# Proiect_TSC_schematic.net
KiCad netlist of a schematic drawn in EAGLE
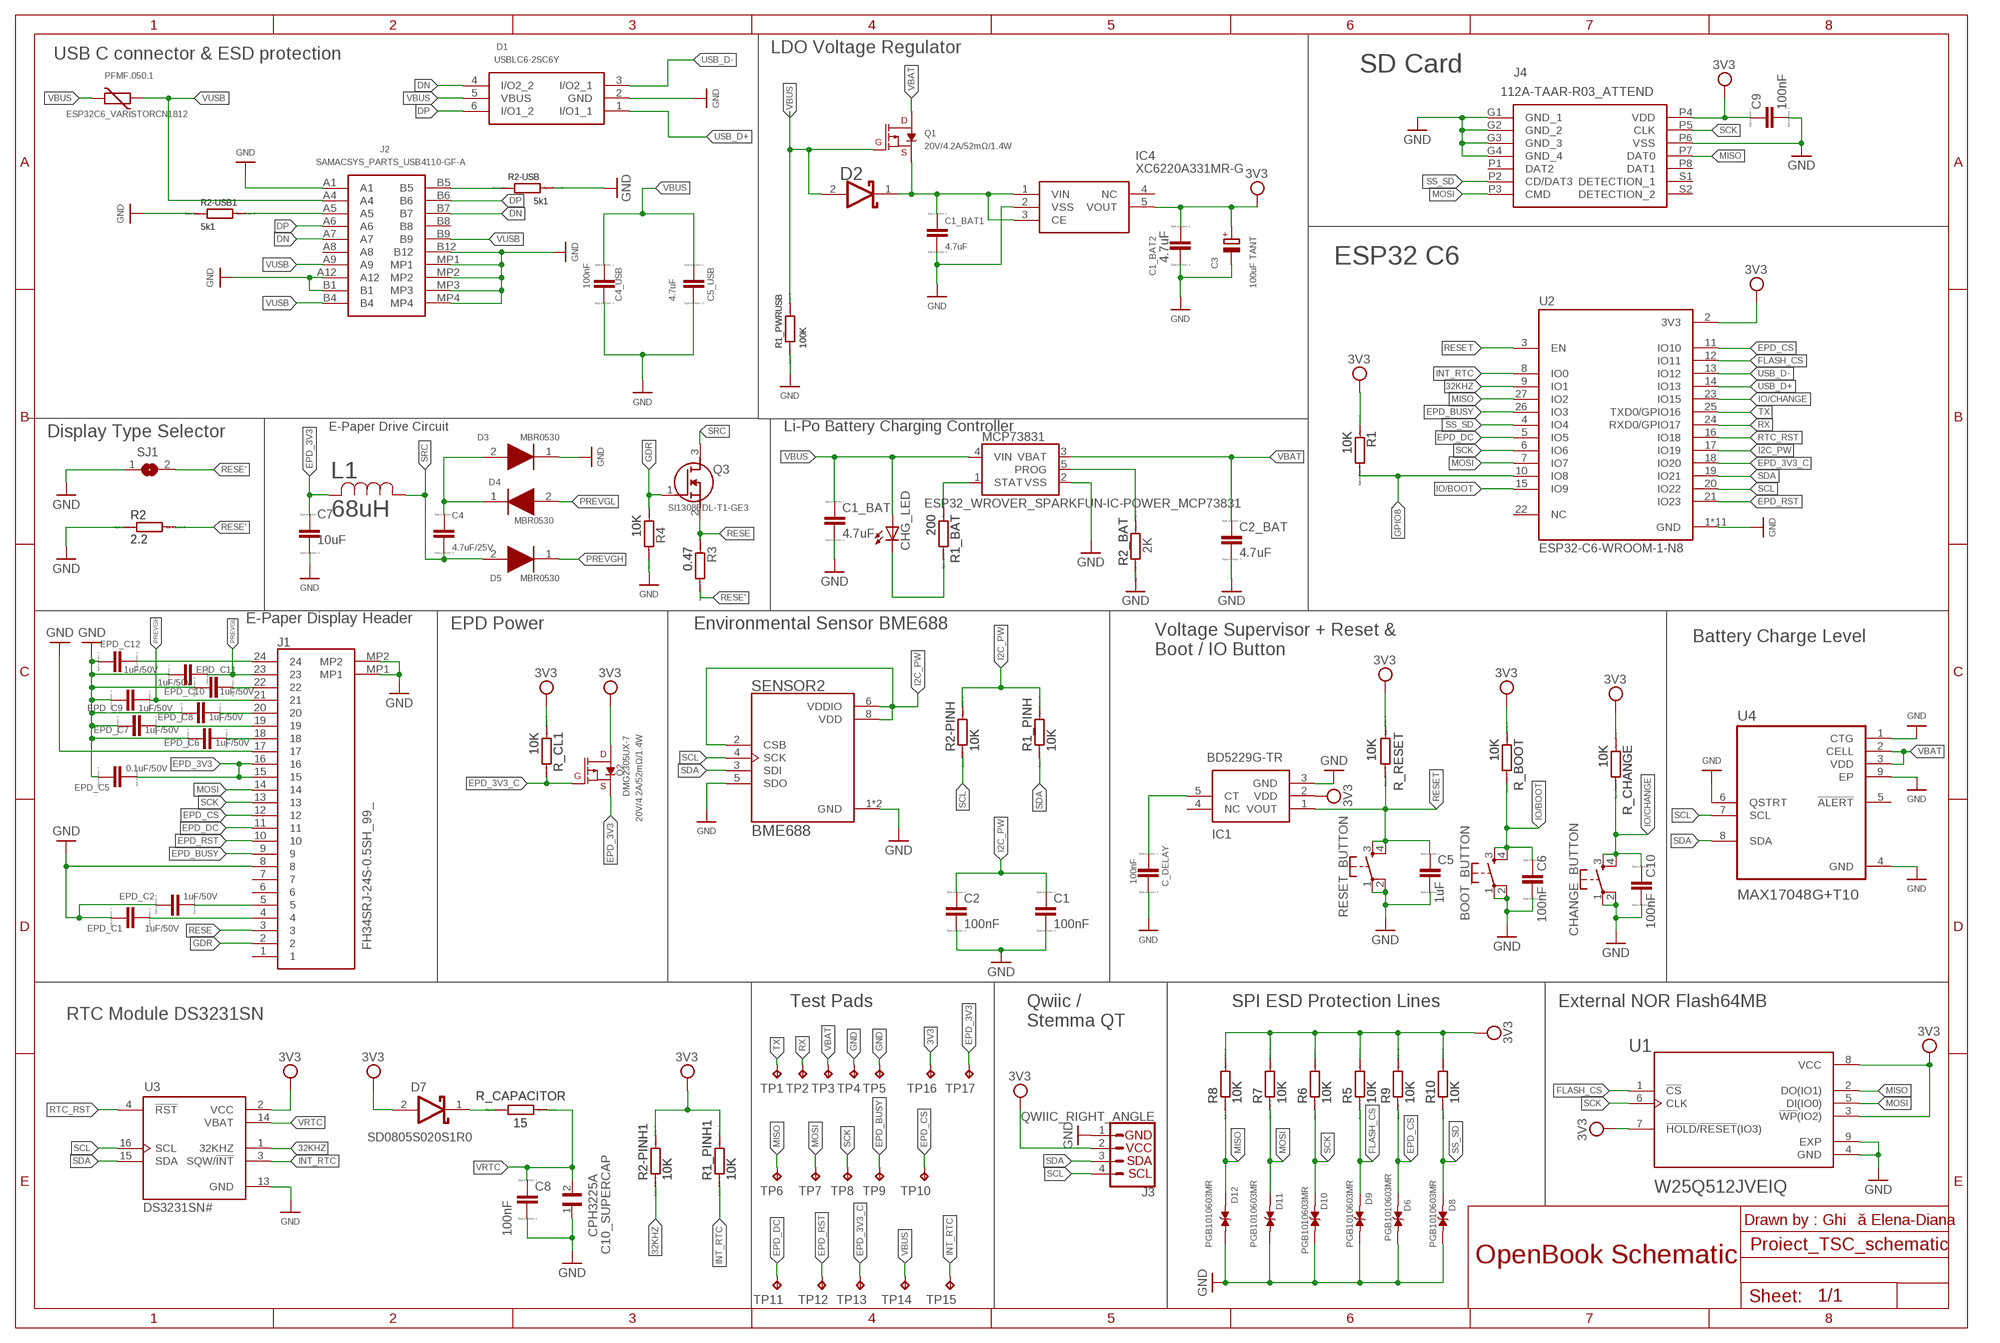
[diagram p0: schematic, sheet 1]

(export (version "E")
  (design (tool "Eeschema 10.0.6"))
  (components
    (comp (ref "BOOT_BUTTON")
      (value "BUTTON_CUSYOMV1")
      (footprint "eagle-import:MYBUTTON")
      (libsource (lib "eagle-import") (part "BUTTON_CUSYOMV1"))
    )
    (comp (ref "C1")
      (value "100nF")
      (footprint "eagle-import:ESP32_WROVER_EAGLE-LTSPICE_C0402")
      (libsource (lib "eagle-import") (part "ESP32_WROVER_EAGLE-LTSPICE_CC0402"))
    )
    (comp (ref "C1_BAT")
      (value "4.7uF")
      (footprint "eagle-import:ESP32_WROVER_EAGLE-LTSPICE_C0402")
      (libsource (lib "eagle-import") (part "ESP32_WROVER_EAGLE-LTSPICE_CC0402"))
    )
    (comp (ref "C1_BAT1")
      (value "4.7uF")
      (footprint "eagle-import:ESP32_WROVER_EAGLE-LTSPICE_C0402")
      (libsource (lib "eagle-import") (part "ESP32_WROVER_EAGLE-LTSPICE_CC0402"))
    )
    (comp (ref "C1_BAT2")
      (value "4.7uF")
      (footprint "eagle-import:ESP32_WROVER_EAGLE-LTSPICE_C0402")
      (libsource (lib "eagle-import") (part "ESP32_WROVER_EAGLE-LTSPICE_CC0402"))
    )
    (comp (ref "C2")
      (value "100nF")
      (footprint "eagle-import:ESP32_WROVER_EAGLE-LTSPICE_C0402")
      (libsource (lib "eagle-import") (part "ESP32_WROVER_EAGLE-LTSPICE_CC0402"))
    )
    (comp (ref "C2_BAT")
      (value "4.7uF")
      (footprint "eagle-import:ESP32_WROVER_EAGLE-LTSPICE_C0402")
      (libsource (lib "eagle-import") (part "ESP32_WROVER_EAGLE-LTSPICE_CC0402"))
    )
    (comp (ref "C3")
      (value "100uF TANT")
      (footprint "eagle-import:RCL_CT3528")
      (libsource (lib "eagle-import") (part "RCL_CPOL-EUCT3528"))
    )
    (comp (ref "C4")
      (value "4.7uF/25V")
      (footprint "eagle-import:ESP32_WROVER_EAGLE-LTSPICE_C0402")
      (libsource (lib "eagle-import") (part "ESP32_WROVER_EAGLE-LTSPICE_CC0402"))
    )
    (comp (ref "C4_USB")
      (value "100nF")
      (footprint "eagle-import:ESP32_WROVER_EAGLE-LTSPICE_C0402")
      (libsource (lib "eagle-import") (part "ESP32_WROVER_EAGLE-LTSPICE_CC0402"))
    )
    (comp (ref "C5")
      (value "1uF")
      (footprint "eagle-import:ESP32_WROVER_EAGLE-LTSPICE_C0402")
      (libsource (lib "eagle-import") (part "ESP32_WROVER_EAGLE-LTSPICE_CC0402"))
    )
    (comp (ref "C5_USB")
      (value "4.7uF")
      (footprint "eagle-import:ESP32_WROVER_EAGLE-LTSPICE_C0402")
      (libsource (lib "eagle-import") (part "ESP32_WROVER_EAGLE-LTSPICE_CC0402"))
    )
    (comp (ref "C6")
      (value "100nF")
      (footprint "eagle-import:ESP32_WROVER_EAGLE-LTSPICE_C0402")
      (libsource (lib "eagle-import") (part "ESP32_WROVER_EAGLE-LTSPICE_CC0402"))
    )
    (comp (ref "C7")
      (value "10uF")
      (footprint "eagle-import:ESP32_WROVER_EAGLE-LTSPICE_C0402")
      (libsource (lib "eagle-import") (part "ESP32_WROVER_EAGLE-LTSPICE_CC0402"))
    )
    (comp (ref "C8")
      (value "100nF")
      (footprint "eagle-import:ESP32_WROVER_EAGLE-LTSPICE_C0402")
      (libsource (lib "eagle-import") (part "ESP32_WROVER_EAGLE-LTSPICE_CC0402"))
    )
    (comp (ref "C9")
      (value "100nF")
      (footprint "eagle-import:ESP32_WROVER_EAGLE-LTSPICE_C0402")
      (libsource (lib "eagle-import") (part "ESP32_WROVER_EAGLE-LTSPICE_CC0402"))
    )
    (comp (ref "C10")
      (value "100nF")
      (footprint "eagle-import:ESP32_WROVER_EAGLE-LTSPICE_C0402")
      (libsource (lib "eagle-import") (part "ESP32_WROVER_EAGLE-LTSPICE_CC0402"))
    )
    (comp (ref "C10_SUPERCAP")
      (value "CPH3225A")
      (footprint "eagle-import:CAPCP3225X100N")
      (fields (field (name "MF") "Seiko Instruments"))
      (libsource (lib "eagle-import") (part "CPH3225A"))
    )
    (comp (ref "CHANGE_BUTTON")
      (value "BUTTON_CUSYOMV1")
      (footprint "eagle-import:MYBUTTON")
      (libsource (lib "eagle-import") (part "BUTTON_CUSYOMV1"))
    )
    (comp (ref "CHG_LED")
      (value "ADAFRUIT_LEDCHIP-LED0603")
      (footprint "eagle-import:ADAFRUIT_CHIP-LED0603")
      (libsource (lib "eagle-import") (part "ADAFRUIT_LEDCHIP-LED0603"))
    )
    (comp (ref "C_DELAY")
      (value "100nF")
      (footprint "eagle-import:ESP32_WROVER_EAGLE-LTSPICE_C0402")
      (libsource (lib "eagle-import") (part "ESP32_WROVER_EAGLE-LTSPICE_CC0402"))
    )
    (comp (ref "D1")
      (value "USBLC6-2SC6Y")
      (footprint "eagle-import:SOT95P280X145-6N")
      (fields (field (name "MF") "STMicroelectronics"))
      (libsource (lib "eagle-import") (part "USBLC6-2SC6Y"))
    )
    (comp (ref "D2")
      (value "ESP32_WROVER_AVX---SD0805S020S1R0_AVX_SD0805S020S1R0_0_0AVX_SD0805S020S1R0_0_0")
      (footprint "eagle-import:ESP32_WROVER_AVX---SD0805S020S1R0_AVX_SD0805S020S1R0_0")
      (fields
        (field (name "DIGIKEY_PART_NUMBER") "478-7800-1-ND")
        (field (name "MF") "AVX")
        (field (name "MOUSER_PART_NUMBER") "581-SD0805S020S1R0")
      )
      (libsource (lib "eagle-import") (part "ESP32_WROVER_AVX---SD0805S020S1R0_AVX_SD0805S020S1R0_0_0AVX_SD0805S020S1R0_0_0"))
    )
    (comp (ref "D3")
      (value "MBR0530")
      (footprint "eagle-import:SOD3716X135N")
      (fields (field (name "MF") "ON Semiconductor"))
      (libsource (lib "eagle-import") (part "MBR0530"))
    )
    (comp (ref "D4")
      (value "MBR0530")
      (footprint "eagle-import:SOD3716X135N")
      (fields (field (name "MF") "ON Semiconductor"))
      (libsource (lib "eagle-import") (part "MBR0530"))
    )
    (comp (ref "D5")
      (value "MBR0530")
      (footprint "eagle-import:SOD3716X135N")
      (fields (field (name "MF") "ON Semiconductor"))
      (libsource (lib "eagle-import") (part "MBR0530"))
    )
    (comp (ref "D6")
      (value "PGB1010603MR")
      (footprint "eagle-import:DIOC1608X36N")
      (fields (field (name "MF") "Littelfuse Inc."))
      (libsource (lib "eagle-import") (part "PGB1010603MR"))
    )
    (comp (ref "D7")
      (value "ESP32_WROVER_AVX---SD0805S020S1R0_AVX_SD0805S020S1R0_0_0AVX_SD0805S020S1R0_0_0")
      (footprint "eagle-import:ESP32_WROVER_AVX---SD0805S020S1R0_AVX_SD0805S020S1R0_0")
      (fields
        (field (name "DIGIKEY_PART_NUMBER") "478-7800-1-ND")
        (field (name "MF") "AVX")
        (field (name "MOUSER_PART_NUMBER") "581-SD0805S020S1R0")
      )
      (libsource (lib "eagle-import") (part "ESP32_WROVER_AVX---SD0805S020S1R0_AVX_SD0805S020S1R0_0_0AVX_SD0805S020S1R0_0_0"))
    )
    (comp (ref "D8")
      (value "PGB1010603MR")
      (footprint "eagle-import:DIOC1608X36N")
      (fields (field (name "MF") "Littelfuse Inc."))
      (libsource (lib "eagle-import") (part "PGB1010603MR"))
    )
    (comp (ref "D9")
      (value "PGB1010603MR")
      (footprint "eagle-import:DIOC1608X36N")
      (fields (field (name "MF") "Littelfuse Inc."))
      (libsource (lib "eagle-import") (part "PGB1010603MR"))
    )
    (comp (ref "D10")
      (value "PGB1010603MR")
      (footprint "eagle-import:DIOC1608X36N")
      (fields (field (name "MF") "Littelfuse Inc."))
      (libsource (lib "eagle-import") (part "PGB1010603MR"))
    )
    (comp (ref "D11")
      (value "PGB1010603MR")
      (footprint "eagle-import:DIOC1608X36N")
      (fields (field (name "MF") "Littelfuse Inc."))
      (libsource (lib "eagle-import") (part "PGB1010603MR"))
    )
    (comp (ref "D12")
      (value "PGB1010603MR")
      (footprint "eagle-import:DIOC1608X36N")
      (fields (field (name "MF") "Littelfuse Inc."))
      (libsource (lib "eagle-import") (part "PGB1010603MR"))
    )
    (comp (ref "EPD_C1")
      (value "1uF/50V")
      (footprint "eagle-import:ESP32_WROVER_EAGLE-LTSPICE_C0402")
      (libsource (lib "eagle-import") (part "ESP32_WROVER_EAGLE-LTSPICE_CC0402"))
    )
    (comp (ref "EPD_C2")
      (value "1uF/50V")
      (footprint "eagle-import:ESP32_WROVER_EAGLE-LTSPICE_C0402")
      (libsource (lib "eagle-import") (part "ESP32_WROVER_EAGLE-LTSPICE_CC0402"))
    )
    (comp (ref "EPD_C5")
      (value "0.1uF/50V")
      (footprint "eagle-import:ESP32_WROVER_EAGLE-LTSPICE_C0402")
      (libsource (lib "eagle-import") (part "ESP32_WROVER_EAGLE-LTSPICE_CC0402"))
    )
    (comp (ref "EPD_C6")
      (value "1uF/50V")
      (footprint "eagle-import:ESP32_WROVER_EAGLE-LTSPICE_C0402")
      (libsource (lib "eagle-import") (part "ESP32_WROVER_EAGLE-LTSPICE_CC0402"))
    )
    (comp (ref "EPD_C7")
      (value "1uF/50V")
      (footprint "eagle-import:ESP32_WROVER_EAGLE-LTSPICE_C0402")
      (libsource (lib "eagle-import") (part "ESP32_WROVER_EAGLE-LTSPICE_CC0402"))
    )
    (comp (ref "EPD_C8")
      (value "1uF/50V")
      (footprint "eagle-import:ESP32_WROVER_EAGLE-LTSPICE_C0402")
      (libsource (lib "eagle-import") (part "ESP32_WROVER_EAGLE-LTSPICE_CC0402"))
    )
    (comp (ref "EPD_C9")
      (value "1uF/50V")
      (footprint "eagle-import:ESP32_WROVER_EAGLE-LTSPICE_C0402")
      (libsource (lib "eagle-import") (part "ESP32_WROVER_EAGLE-LTSPICE_CC0402"))
    )
    (comp (ref "EPD_C10")
      (value "1uF/50V")
      (footprint "eagle-import:ESP32_WROVER_EAGLE-LTSPICE_C0402")
      (libsource (lib "eagle-import") (part "ESP32_WROVER_EAGLE-LTSPICE_CC0402"))
    )
    (comp (ref "EPD_C11")
      (value "1uF/50V")
      (footprint "eagle-import:ESP32_WROVER_EAGLE-LTSPICE_C0402")
      (libsource (lib "eagle-import") (part "ESP32_WROVER_EAGLE-LTSPICE_CC0402"))
    )
    (comp (ref "EPD_C12")
      (value "1uF/50V")
      (footprint "eagle-import:ESP32_WROVER_EAGLE-LTSPICE_C0402")
      (libsource (lib "eagle-import") (part "ESP32_WROVER_EAGLE-LTSPICE_CC0402"))
    )
    (comp (ref "IC1")
      (value "BD5229G-TR")
      (footprint "eagle-import:SOT95P280X125-5N")
      (fields (field (name "MOUSER_PART_NUMBER") "755-BD5229G-TR"))
      (libsource (lib "eagle-import") (part "BD5229G-TR"))
    )
    (comp (ref "IC4")
      (value "XC6220A331MR-G")
      (footprint "eagle-import:SOT95P280X120-5N")
      (fields (field (name "MOUSER_PART_NUMBER") "865-XC6220A331MR-G"))
      (libsource (lib "eagle-import") (part "XC6220A331MR-G"))
    )
    (comp (ref "J1")
      (value "FH34SRJ-24S-0.5SH_99_")
      (footprint "eagle-import:FH34SRJ24S05SH99")
      (fields
        (field (name "MANUFACTURER_PART_NUMBER") "FH34SRJ-24S-0.5SH(99)")
        (field (name "MOUSER_PART_NUMBER") "798-FH34SRJ24S05SH99")
      )
      (libsource (lib "eagle-import") (part "FH34SRJ-24S-0.5SH_99_"))
    )
    (comp (ref "J2")
      (value "SAMACSYS_PARTS_USB4110-GF-A")
      (footprint "eagle-import:SAMACSYS_PARTS_USB4110GFA")
      (fields
        (field (name "MANUFACTURER_PART_NUMBER") "USB4110-GF-A")
        (field (name "MOUSER_PART_NUMBER") "640-USB4110-GF-A")
      )
      (libsource (lib "eagle-import") (part "SAMACSYS_PARTS_USB4110-GF-A"))
    )
    (comp (ref "J3")
      (value "QWIIC_RIGHT_ANGLE")
      (footprint "eagle-import:JST04_1MM_RA")
      (libsource (lib "eagle-import") (part "QWIIC_CONNECTORJS-1MM"))
    )
    (comp (ref "J4")
      (value "112A-TAAR-R03_ATTEND")
      (footprint "eagle-import:112ATAARR03ATTEND")
      (fields (field (name "MANUFACTURER_PART_NUMBER") "112A-TAAR-R03 ATTEND"))
      (libsource (lib "eagle-import") (part "112A-TAAR-R03_ATTEND"))
    )
    (comp (ref "L1")
      (value "68uH")
      (footprint "eagle-import:IND_4828-WE-TPC_WRE")
      (fields
        (field (name "MANUFACTURER_PART_NUMBER") "744043680")
        (field (name "COPYRIGHT") "Copyright (C) 2024 Ultra Librarian. All rights reserved.")
      )
      (libsource (lib "eagle-import") (part "744043680IND_4828-WE-TPC_WRE"))
    )
    (comp (ref "MCP73831")
      (value "ESP32_WROVER_SPARKFUN-IC-POWER_MCP73831")
      (footprint "eagle-import:ESP32_WROVER_SPARKFUN-IC-POWER_SOT23-5")
      (libsource (lib "eagle-import") (part "ESP32_WROVER_SPARKFUN-IC-POWER_MCP73831"))
    )
    (comp (ref "PFMF.050.1")
      (value "ESP32C6_VARISTORCN1812")
      (footprint "eagle-import:ESP32C6_VARISTOR_CT_CN1812")
      (libsource (lib "eagle-import") (part "ESP32C6_VARISTORCN1812"))
    )
    (comp (ref "Q1")
      (value "20V/4.2A/52mΩ/1.4W")
      (footprint "eagle-import:ESP32_WROVER_SPARKFUN-DISCRETESEMI_SOT23-3")
      (libsource (lib "eagle-import") (part "ESP32_WROVER_SPARKFUN-DISCRETESEMI_MOSFET_PCH-DMG2305UX-7"))
    )
    (comp (ref "Q2")
      (value "20V/4.2A/52mΩ/1.4W")
      (footprint "eagle-import:ESP32_WROVER_SPARKFUN-DISCRETESEMI_SOT23-3")
      (fields (field (name "THERMALLOSS") "2305 UX"))
      (libsource (lib "eagle-import") (part "ESP32_WROVER_SPARKFUN-DISCRETESEMI_MOSFET_PCH-DMG2305UX-7"))
    )
    (comp (ref "Q3")
      (value "SI1308EDL-T1-GE3")
      (footprint "eagle-import:SOT65P210X110-3N")
      (fields (field (name "MF") "Vishay Siliconix"))
      (libsource (lib "eagle-import") (part "SI1308EDL-T1-GE3"))
    )
    (comp (ref "R1")
      (value "10K")
      (footprint "eagle-import:ESP32_WROVER_EAGLE-LTSPICE_R0402")
      (libsource (lib "eagle-import") (part "ESP32_WROVER_EAGLE-LTSPICE_RR0402"))
    )
    (comp (ref "R1_BAT")
      (value "200")
      (footprint "eagle-import:ESP32_WROVER_EAGLE-LTSPICE_R0402")
      (libsource (lib "eagle-import") (part "ESP32_WROVER_EAGLE-LTSPICE_RR0402"))
    )
    (comp (ref "R1_PINH")
      (value "10K")
      (footprint "eagle-import:ESP32_WROVER_EAGLE-LTSPICE_R0402")
      (libsource (lib "eagle-import") (part "ESP32_WROVER_EAGLE-LTSPICE_RR0402"))
    )
    (comp (ref "R1_PINH1")
      (value "10K")
      (footprint "eagle-import:ESP32_WROVER_EAGLE-LTSPICE_R0402")
      (libsource (lib "eagle-import") (part "ESP32_WROVER_EAGLE-LTSPICE_RR0402"))
    )
    (comp (ref "R1_PWRUSB")
      (value "100K")
      (footprint "eagle-import:ESP32_WROVER_EAGLE-LTSPICE_R0402")
      (libsource (lib "eagle-import") (part "ESP32_WROVER_EAGLE-LTSPICE_RR0402"))
    )
    (comp (ref "R2")
      (value "2.2")
      (footprint "eagle-import:ESP32_WROVER_EAGLE-LTSPICE_R0402")
      (libsource (lib "eagle-import") (part "ESP32_WROVER_EAGLE-LTSPICE_RR0402"))
    )
    (comp (ref "R2-PINH")
      (value "10K")
      (footprint "eagle-import:ESP32_WROVER_EAGLE-LTSPICE_R0402")
      (libsource (lib "eagle-import") (part "ESP32_WROVER_EAGLE-LTSPICE_RR0402"))
    )
    (comp (ref "R2-PINH1")
      (value "10K")
      (footprint "eagle-import:ESP32_WROVER_EAGLE-LTSPICE_R0402")
      (libsource (lib "eagle-import") (part "ESP32_WROVER_EAGLE-LTSPICE_RR0402"))
    )
    (comp (ref "R2-USB")
      (value "5k1")
      (footprint "eagle-import:ESP32_WROVER_EAGLE-LTSPICE_R0402")
      (libsource (lib "eagle-import") (part "ESP32_WROVER_EAGLE-LTSPICE_RR0402"))
    )
    (comp (ref "R2-USB1")
      (value "5k1")
      (footprint "eagle-import:ESP32_WROVER_EAGLE-LTSPICE_R0402")
      (libsource (lib "eagle-import") (part "ESP32_WROVER_EAGLE-LTSPICE_RR0402"))
    )
    (comp (ref "R2_BAT")
      (value "2K")
      (footprint "eagle-import:ESP32_WROVER_EAGLE-LTSPICE_R0402")
      (libsource (lib "eagle-import") (part "ESP32_WROVER_EAGLE-LTSPICE_RR0402"))
    )
    (comp (ref "R3")
      (value "0.47")
      (footprint "eagle-import:ESP32_WROVER_EAGLE-LTSPICE_R0402")
      (libsource (lib "eagle-import") (part "ESP32_WROVER_EAGLE-LTSPICE_RR0402"))
    )
    (comp (ref "R4")
      (value "10K")
      (footprint "eagle-import:ESP32_WROVER_EAGLE-LTSPICE_R0402")
      (libsource (lib "eagle-import") (part "ESP32_WROVER_EAGLE-LTSPICE_RR0402"))
    )
    (comp (ref "R5")
      (value "10K")
      (footprint "eagle-import:ESP32_WROVER_EAGLE-LTSPICE_R0402")
      (libsource (lib "eagle-import") (part "ESP32_WROVER_EAGLE-LTSPICE_RR0402"))
    )
    (comp (ref "R6")
      (value "10K")
      (footprint "eagle-import:ESP32_WROVER_EAGLE-LTSPICE_R0402")
      (libsource (lib "eagle-import") (part "ESP32_WROVER_EAGLE-LTSPICE_RR0402"))
    )
    (comp (ref "R7")
      (value "10K")
      (footprint "eagle-import:ESP32_WROVER_EAGLE-LTSPICE_R0402")
      (libsource (lib "eagle-import") (part "ESP32_WROVER_EAGLE-LTSPICE_RR0402"))
    )
    (comp (ref "R8")
      (value "10K")
      (footprint "eagle-import:ESP32_WROVER_EAGLE-LTSPICE_R0402")
      (libsource (lib "eagle-import") (part "ESP32_WROVER_EAGLE-LTSPICE_RR0402"))
    )
    (comp (ref "R9")
      (value "10K")
      (footprint "eagle-import:ESP32_WROVER_EAGLE-LTSPICE_R0402")
      (libsource (lib "eagle-import") (part "ESP32_WROVER_EAGLE-LTSPICE_RR0402"))
    )
    (comp (ref "R10")
      (value "10K")
      (footprint "eagle-import:ESP32_WROVER_EAGLE-LTSPICE_R0402")
      (libsource (lib "eagle-import") (part "ESP32_WROVER_EAGLE-LTSPICE_RR0402"))
    )
    (comp (ref "RESET_BUTTON")
      (value "BUTTON_CUSYOMV1")
      (footprint "eagle-import:MYBUTTON")
      (libsource (lib "eagle-import") (part "BUTTON_CUSYOMV1"))
    )
    (comp (ref "R_BOOT")
      (value "10K")
      (footprint "eagle-import:ESP32_WROVER_EAGLE-LTSPICE_R0402")
      (libsource (lib "eagle-import") (part "ESP32_WROVER_EAGLE-LTSPICE_RR0402"))
    )
    (comp (ref "R_CAPACITOR")
      (value "15")
      (footprint "eagle-import:ESP32_WROVER_EAGLE-LTSPICE_R0402")
      (libsource (lib "eagle-import") (part "ESP32_WROVER_EAGLE-LTSPICE_RR0402"))
    )
    (comp (ref "R_CHANGE")
      (value "10K")
      (footprint "eagle-import:ESP32_WROVER_EAGLE-LTSPICE_R0402")
      (libsource (lib "eagle-import") (part "ESP32_WROVER_EAGLE-LTSPICE_RR0402"))
    )
    (comp (ref "R_CL1")
      (value "10K")
      (footprint "eagle-import:ESP32_WROVER_EAGLE-LTSPICE_R0402")
      (libsource (lib "eagle-import") (part "ESP32_WROVER_EAGLE-LTSPICE_RR0402"))
    )
    (comp (ref "R_RESET")
      (value "10K")
      (footprint "eagle-import:ESP32_WROVER_EAGLE-LTSPICE_R0402")
      (libsource (lib "eagle-import") (part "ESP32_WROVER_EAGLE-LTSPICE_RR0402"))
    )
    (comp (ref "SENSOR2")
      (value "BME688")
      (footprint "eagle-import:ESP32_WROVER_BME680_PSON80P300X300X100-8N")
      (fields (field (name "MF") "Bosch Sensortec") (field (name "MP") "BME680"))
      (libsource (lib "eagle-import") (part "ESP32_WROVER_BME680_BME680"))
    )
    (comp (ref "SJ1") (value "SJ") (footprint "eagle-import:SJ") (libsource (lib "eagle-import") (part "SJ")))
    (comp (ref "TP1")
      (value "TPTP20R")
      (footprint "eagle-import:TP20R")
      (libsource (lib "eagle-import") (part "TPTP20R"))
    )
    (comp (ref "TP2")
      (value "TPTP20R")
      (footprint "eagle-import:TP20R")
      (libsource (lib "eagle-import") (part "TPTP20R"))
    )
    (comp (ref "TP3")
      (value "TPTP20R")
      (footprint "eagle-import:TP20R")
      (libsource (lib "eagle-import") (part "TPTP20R"))
    )
    (comp (ref "TP4")
      (value "TPTP20R")
      (footprint "eagle-import:TP20R")
      (libsource (lib "eagle-import") (part "TPTP20R"))
    )
    (comp (ref "TP5")
      (value "TPTP20R")
      (footprint "eagle-import:TP20R")
      (libsource (lib "eagle-import") (part "TPTP20R"))
    )
    (comp (ref "TP6")
      (value "TPTP20R")
      (footprint "eagle-import:TP20R")
      (libsource (lib "eagle-import") (part "TPTP20R"))
    )
    (comp (ref "TP7")
      (value "TPTP20R")
      (footprint "eagle-import:TP20R")
      (libsource (lib "eagle-import") (part "TPTP20R"))
    )
    (comp (ref "TP8")
      (value "TPTP20R")
      (footprint "eagle-import:TP20R")
      (libsource (lib "eagle-import") (part "TPTP20R"))
    )
    (comp (ref "TP9")
      (value "TPTP20R")
      (footprint "eagle-import:TP20R")
      (libsource (lib "eagle-import") (part "TPTP20R"))
    )
    (comp (ref "TP10")
      (value "TPTP20R")
      (footprint "eagle-import:TP20R")
      (libsource (lib "eagle-import") (part "TPTP20R"))
    )
    (comp (ref "TP11")
      (value "TPTP20R")
      (footprint "eagle-import:TP20R")
      (libsource (lib "eagle-import") (part "TPTP20R"))
    )
    (comp (ref "TP12")
      (value "TPTP20R")
      (footprint "eagle-import:TP20R")
      (libsource (lib "eagle-import") (part "TPTP20R"))
    )
    (comp (ref "TP13")
      (value "TPTP20R")
      (footprint "eagle-import:TP20R")
      (libsource (lib "eagle-import") (part "TPTP20R"))
    )
    (comp (ref "TP14")
      (value "TPTP20R")
      (footprint "eagle-import:TP20R")
      (libsource (lib "eagle-import") (part "TPTP20R"))
    )
    (comp (ref "TP15")
      (value "TPTP20R")
      (footprint "eagle-import:TP20R")
      (libsource (lib "eagle-import") (part "TPTP20R"))
    )
    (comp (ref "TP16")
      (value "TPTP20R")
      (footprint "eagle-import:TP20R")
      (libsource (lib "eagle-import") (part "TPTP20R"))
    )
    (comp (ref "TP17")
      (value "TPTP20R")
      (footprint "eagle-import:TP20R")
      (libsource (lib "eagle-import") (part "TPTP20R"))
    )
    (comp (ref "U1")
      (value "W25Q512JVEIQ")
      (footprint "eagle-import:SON127P600X800X80-9N")
      (fields (field (name "MF") "Winbond Electronics"))
      (libsource (lib "eagle-import") (part "W25Q512JVEIQ"))
    )
    (comp (ref "U2")
      (value "ESP32-C6-WROOM-1-N8")
      (footprint "eagle-import:XCVR_ESP32-C6-WROOM-1-N8")
      (fields (field (name "MF") "Espressif Systems"))
      (libsource (lib "eagle-import") (part "ESP32-C6-WROOM-1-N8"))
    )
    (comp (ref "U3")
      (value "DS3231SN#")
      (footprint "eagle-import:SOIC127P1032X265-16N")
      (fields (field (name "MF") "Analog Devices"))
      (libsource (lib "eagle-import") (part "DS3231SN#"))
    )
    (comp (ref "U4")
      (value "MAX17048G+T10")
      (footprint "eagle-import:SON50P200X200X80-9N")
      (fields (field (name "MF") "Analog Devices"))
      (libsource (lib "eagle-import") (part "MAX17048G+T10"))
    )
  )
  (nets
    (net (code "1") (name "3V3") (class "Default")
      (node (ref "C1_BAT2") (pin "1") (pinfunction "1_1") (pintype "passive"))
      (node (ref "C3") (pin "+") (pinfunction "+_+") (pintype "passive"))
      (node (ref "C9") (pin "1") (pinfunction "1_1") (pintype "passive"))
      (node (ref "D7") (pin "2") (pinfunction "ANODE_2") (pintype "bidirectional"))
      (node (ref "IC1") (pin "2") (pinfunction "VDD_2") (pintype "bidirectional"))
      (node (ref "IC4") (pin "5") (pinfunction "VOUT_5") (pintype "bidirectional"))
      (node (ref "J3") (pin "2") (pinfunction "2_2") (pintype "power_in"))
      (node (ref "J4") (pin "P4") (pinfunction "VDD_P4") (pintype "bidirectional"))
      (node (ref "Q2") (pin "3") (pinfunction "D_3") (pintype "bidirectional"))
      (node (ref "R1") (pin "1") (pinfunction "1_1") (pintype "passive"))
      (node (ref "R10") (pin "2") (pinfunction "2_2") (pintype "passive"))
      (node (ref "R1_PINH1") (pin "2") (pinfunction "2_2") (pintype "passive"))
      (node (ref "R2-PINH1") (pin "2") (pinfunction "2_2") (pintype "passive"))
      (node (ref "R5") (pin "2") (pinfunction "2_2") (pintype "passive"))
      (node (ref "R6") (pin "2") (pinfunction "2_2") (pintype "passive"))
      (node (ref "R7") (pin "2") (pinfunction "2_2") (pintype "passive"))
      (node (ref "R8") (pin "2") (pinfunction "2_2") (pintype "passive"))
      (node (ref "R9") (pin "2") (pinfunction "2_2") (pintype "passive"))
      (node (ref "R_BOOT") (pin "1") (pinfunction "1_1") (pintype "passive"))
      (node (ref "R_CHANGE") (pin "1") (pinfunction "1_1") (pintype "passive"))
      (node (ref "R_CL1") (pin "1") (pinfunction "1_1") (pintype "passive"))
      (node (ref "R_RESET") (pin "1") (pinfunction "1_1") (pintype "passive"))
      (node (ref "TP16") (pin "TP") (pinfunction "TP_TP") (pintype "input"))
      (node (ref "U1") (pin "3") (pinfunction "~{WP}(IO2)_3") (pintype "bidirectional"))
      (node (ref "U1") (pin "7") (pinfunction "~{HOLD}/~{RESET}(IO3)_7") (pintype "bidirectional"))
      (node (ref "U1") (pin "8") (pinfunction "VCC_8") (pintype "power_in"))
      (node (ref "U2") (pin "2") (pinfunction "3V3_2") (pintype "power_in"))
      (node (ref "U3") (pin "2") (pinfunction "VCC_2") (pintype "power_in"))
    )
    (net (code "2") (name "32KHZ") (class "Default")
      (node (ref "R2-PINH1") (pin "1") (pinfunction "1_1") (pintype "passive"))
      (node (ref "U2") (pin "9") (pinfunction "IO1_9") (pintype "bidirectional"))
      (node (ref "U3") (pin "1") (pinfunction "32KHZ_1") (pintype "output"))
    )
    (net (code "3") (name "DN") (class "Default")
      (node (ref "D1") (pin "4") (pinfunction "I/O2_2_4") (pintype "bidirectional"))
      (node (ref "J2") (pin "A7") (pinfunction "A7_A7") (pintype "bidirectional"))
      (node (ref "J2") (pin "B7") (pinfunction "B7_B7") (pintype "bidirectional"))
    )
    (net (code "4") (name "DP") (class "Default")
      (node (ref "D1") (pin "6") (pinfunction "I/O1_2_6") (pintype "bidirectional"))
      (node (ref "J2") (pin "A6") (pinfunction "A6_A6") (pintype "bidirectional"))
      (node (ref "J2") (pin "B6") (pinfunction "B6_B6") (pintype "bidirectional"))
    )
    (net (code "5") (name "EPD_3V3") (class "Default")
      (node (ref "C7") (pin "1") (pinfunction "1_1") (pintype "passive"))
      (node (ref "EPD_C5") (pin "1") (pinfunction "1_1") (pintype "passive"))
      (node (ref "J1") (pin "15") (pinfunction "15_15") (pintype "bidirectional"))
      (node (ref "J1") (pin "16") (pinfunction "16_16") (pintype "bidirectional"))
      (node (ref "L1") (pin "2") (pinfunction "2_2") (pintype "passive"))
      (node (ref "Q2") (pin "2") (pinfunction "S_2") (pintype "bidirectional"))
      (node (ref "TP17") (pin "TP") (pinfunction "TP_TP") (pintype "input"))
    )
    (net (code "6") (name "EPD_3V3_C") (class "Default")
      (node (ref "Q2") (pin "1") (pinfunction "G_1") (pintype "bidirectional"))
      (node (ref "R_CL1") (pin "2") (pinfunction "2_2") (pintype "passive"))
      (node (ref "TP13") (pin "TP") (pinfunction "TP_TP") (pintype "input"))
      (node (ref "U2") (pin "18") (pinfunction "IO20_18") (pintype "bidirectional"))
    )
    (net (code "7") (name "EPD_BUSY") (class "Default")
      (node (ref "J1") (pin "9") (pinfunction "9_9") (pintype "bidirectional"))
      (node (ref "TP9") (pin "TP") (pinfunction "TP_TP") (pintype "input"))
      (node (ref "U2") (pin "26") (pinfunction "IO3_26") (pintype "bidirectional"))
    )
    (net (code "8") (name "EPD_CS") (class "Default")
      (node (ref "D6") (pin "1") (pinfunction "1_1") (pintype "passive"))
      (node (ref "J1") (pin "12") (pinfunction "12_12") (pintype "bidirectional"))
      (node (ref "R9") (pin "1") (pinfunction "1_1") (pintype "passive"))
      (node (ref "TP10") (pin "TP") (pinfunction "TP_TP") (pintype "input"))
      (node (ref "U2") (pin "11") (pinfunction "IO10_11") (pintype "bidirectional"))
    )
    (net (code "9") (name "EPD_DC") (class "Default")
      (node (ref "J1") (pin "11") (pinfunction "11_11") (pintype "bidirectional"))
      (node (ref "TP11") (pin "TP") (pinfunction "TP_TP") (pintype "input"))
      (node (ref "U2") (pin "5") (pinfunction "IO5_5") (pintype "bidirectional"))
    )
    (net (code "10") (name "EPD_RST") (class "Default")
      (node (ref "J1") (pin "10") (pinfunction "10_10") (pintype "bidirectional"))
      (node (ref "TP12") (pin "TP") (pinfunction "TP_TP") (pintype "input"))
      (node (ref "U2") (pin "21") (pinfunction "IO23_21") (pintype "bidirectional"))
    )
    (net (code "11") (name "FLASH_CS") (class "Default")
      (node (ref "D9") (pin "1") (pinfunction "1_1") (pintype "passive"))
      (node (ref "R5") (pin "1") (pinfunction "1_1") (pintype "passive"))
      (node (ref "U1") (pin "1") (pinfunction "~{CS}_1") (pintype "input"))
      (node (ref "U2") (pin "12") (pinfunction "IO11_12") (pintype "bidirectional"))
    )
    (net (code "12") (name "GDR") (class "Default")
      (node (ref "J1") (pin "2") (pinfunction "2_2") (pintype "bidirectional"))
      (node (ref "Q3") (pin "1") (pinfunction "G_1") (pintype "bidirectional"))
      (node (ref "R4") (pin "1") (pinfunction "1_1") (pintype "passive"))
    )
    (net (code "13") (name "GND") (class "Default")
      (node (ref "BOOT_BUTTON") (pin "1") (pinfunction "1_1") (pintype "passive"))
      (node (ref "BOOT_BUTTON") (pin "2") (pinfunction "2_2") (pintype "passive"))
      (node (ref "C1") (pin "2") (pinfunction "2_2") (pintype "passive"))
      (node (ref "C10") (pin "2") (pinfunction "2_2") (pintype "passive"))
      (node (ref "C10_SUPERCAP") (pin "1") (pinfunction "1_1") (pintype "passive"))
      (node (ref "C1_BAT") (pin "2") (pinfunction "2_2") (pintype "passive"))
      (node (ref "C1_BAT1") (pin "2") (pinfunction "2_2") (pintype "passive"))
      (node (ref "C1_BAT2") (pin "2") (pinfunction "2_2") (pintype "passive"))
      (node (ref "C2") (pin "2") (pinfunction "2_2") (pintype "passive"))
      (node (ref "C2_BAT") (pin "2") (pinfunction "2_2") (pintype "passive"))
      (node (ref "C3") (pin "-") (pinfunction "-_-") (pintype "passive"))
      (node (ref "C4_USB") (pin "2") (pinfunction "2_2") (pintype "passive"))
      (node (ref "C5") (pin "2") (pinfunction "2_2") (pintype "passive"))
      (node (ref "C5_USB") (pin "2") (pinfunction "2_2") (pintype "passive"))
      (node (ref "C6") (pin "2") (pinfunction "2_2") (pintype "passive"))
      (node (ref "C7") (pin "2") (pinfunction "2_2") (pintype "passive"))
      (node (ref "C8") (pin "2") (pinfunction "2_2") (pintype "passive"))
      (node (ref "C9") (pin "2") (pinfunction "2_2") (pintype "passive"))
      (node (ref "CHANGE_BUTTON") (pin "1") (pinfunction "1_1") (pintype "passive"))
      (node (ref "CHANGE_BUTTON") (pin "2") (pinfunction "2_2") (pintype "passive"))
      (node (ref "C_DELAY") (pin "2") (pinfunction "2_2") (pintype "passive"))
      (node (ref "D1") (pin "2") (pinfunction "GND_2") (pintype "bidirectional"))
      (node (ref "D10") (pin "2") (pinfunction "2_2") (pintype "passive"))
      (node (ref "D11") (pin "2") (pinfunction "2_2") (pintype "passive"))
      (node (ref "D12") (pin "2") (pinfunction "2_2") (pintype "passive"))
      (node (ref "D3") (pin "1") (pinfunction "K_1") (pintype "bidirectional"))
      (node (ref "D6") (pin "2") (pinfunction "2_2") (pintype "passive"))
      (node (ref "D8") (pin "2") (pinfunction "2_2") (pintype "passive"))
      (node (ref "D9") (pin "2") (pinfunction "2_2") (pintype "passive"))
      (node (ref "EPD_C1") (pin "2") (pinfunction "2_2") (pintype "passive"))
      (node (ref "EPD_C10") (pin "2") (pinfunction "2_2") (pintype "passive"))
      (node (ref "EPD_C11") (pin "2") (pinfunction "2_2") (pintype "passive"))
      (node (ref "EPD_C12") (pin "2") (pinfunction "2_2") (pintype "passive"))
      (node (ref "EPD_C2") (pin "2") (pinfunction "2_2") (pintype "passive"))
      (node (ref "EPD_C5") (pin "2") (pinfunction "2_2") (pintype "passive"))
      (node (ref "EPD_C6") (pin "2") (pinfunction "2_2") (pintype "passive"))
      (node (ref "EPD_C7") (pin "2") (pinfunction "2_2") (pintype "passive"))
      (node (ref "EPD_C8") (pin "2") (pinfunction "2_2") (pintype "passive"))
      (node (ref "EPD_C9") (pin "2") (pinfunction "2_2") (pintype "passive"))
      (node (ref "IC1") (pin "3") (pinfunction "GND_3") (pintype "bidirectional"))
      (node (ref "IC4") (pin "2") (pinfunction "VSS_2") (pintype "bidirectional"))
      (node (ref "J1") (pin "17") (pinfunction "17_17") (pintype "bidirectional"))
      (node (ref "J1") (pin "8") (pinfunction "8_8") (pintype "bidirectional"))
      (node (ref "J1") (pin "MP1") (pinfunction "MP1_MP1") (pintype "bidirectional"))
      (node (ref "J1") (pin "MP2") (pinfunction "MP2_MP2") (pintype "bidirectional"))
      (node (ref "J2") (pin "A1") (pinfunction "A1_A1") (pintype "bidirectional"))
      (node (ref "J2") (pin "A12") (pinfunction "A12_A12") (pintype "bidirectional"))
      (node (ref "J2") (pin "B1") (pinfunction "B1_B1") (pintype "bidirectional"))
      (node (ref "J2") (pin "B12") (pinfunction "B12_B12") (pintype "bidirectional"))
      (node (ref "J2") (pin "MP1") (pinfunction "MP1_MP1") (pintype "bidirectional"))
      (node (ref "J2") (pin "MP2") (pinfunction "MP2_MP2") (pintype "bidirectional"))
      (node (ref "J2") (pin "MP3") (pinfunction "MP3_MP3") (pintype "bidirectional"))
      (node (ref "J2") (pin "MP4") (pinfunction "MP4_MP4") (pintype "bidirectional"))
      (node (ref "J3") (pin "1") (pinfunction "1_1") (pintype "power_in"))
      (node (ref "J4") (pin "G1") (pinfunction "GND_1_G1") (pintype "bidirectional"))
      (node (ref "J4") (pin "G2") (pinfunction "GND_2_G2") (pintype "bidirectional"))
      (node (ref "J4") (pin "G3") (pinfunction "GND_3_G3") (pintype "bidirectional"))
      (node (ref "J4") (pin "G4") (pinfunction "GND_4_G4") (pintype "bidirectional"))
      (node (ref "J4") (pin "P6") (pinfunction "VSS_P6") (pintype "bidirectional"))
      (node (ref "MCP73831") (pin "2") (pinfunction "VSS_2") (pintype "power_in"))
      (node (ref "R1_PWRUSB") (pin "1") (pinfunction "1_1") (pintype "passive"))
      (node (ref "R2") (pin "1") (pinfunction "1_1") (pintype "passive"))
      (node (ref "R2-USB") (pin "2") (pinfunction "2_2") (pintype "passive"))
      (node (ref "R2-USB1") (pin "1") (pinfunction "1_1") (pintype "passive"))
      (node (ref "R2_BAT") (pin "1") (pinfunction "1_1") (pintype "passive"))
      (node (ref "R4") (pin "2") (pinfunction "2_2") (pintype "passive"))
      (node (ref "RESET_BUTTON") (pin "1") (pinfunction "1_1") (pintype "passive"))
      (node (ref "RESET_BUTTON") (pin "2") (pinfunction "2_2") (pintype "passive"))
      (node (ref "SENSOR2") (pin "1") (pinfunction "GND_1") (pintype "power_in"))
      (node (ref "SENSOR2") (pin "5") (pinfunction "SDO_5") (pintype "bidirectional"))
      (node (ref "SENSOR2") (pin "7") (pinfunction "GND_7") (pintype "power_in"))
      (node (ref "SJ1") (pin "1") (pinfunction "1_1") (pintype "passive"))
      (node (ref "TP4") (pin "TP") (pinfunction "TP_TP") (pintype "input"))
      (node (ref "TP5") (pin "TP") (pinfunction "TP_TP") (pintype "input"))
      (node (ref "U1") (pin "4") (pinfunction "GND_4") (pintype "power_in"))
      (node (ref "U1") (pin "9") (pinfunction "EXP_9") (pintype "passive"))
      (node (ref "U2") (pin "1") (pinfunction "GND_1") (pintype "power_in"))
      (node (ref "U2") (pin "28") (pinfunction "GND_28") (pintype "power_in"))
      (node (ref "U2") (pin "29_1") (pinfunction "GND_29_1") (pintype "power_in"))
      (node (ref "U2") (pin "29_2") (pinfunction "GND_29_2") (pintype "power_in"))
      (node (ref "U2") (pin "29_3") (pinfunction "GND_29_3") (pintype "power_in"))
      (node (ref "U2") (pin "29_4") (pinfunction "GND_29_4") (pintype "power_in"))
      (node (ref "U2") (pin "29_5") (pinfunction "GND_29_5") (pintype "power_in"))
      (node (ref "U2") (pin "29_6") (pinfunction "GND_29_6") (pintype "power_in"))
      (node (ref "U2") (pin "29_7") (pinfunction "GND_29_7") (pintype "power_in"))
      (node (ref "U2") (pin "29_8") (pinfunction "GND_29_8") (pintype "power_in"))
      (node (ref "U2") (pin "29_9") (pinfunction "GND_29_9") (pintype "power_in"))
      (node (ref "U3") (pin "13") (pinfunction "GND_13") (pintype "power_in"))
      (node (ref "U4") (pin "1") (pinfunction "CTG_1") (pintype "power_in"))
      (node (ref "U4") (pin "4") (pinfunction "GND_4") (pintype "power_in"))
      (node (ref "U4") (pin "6") (pinfunction "QSTRT_6") (pintype "input"))
      (node (ref "U4") (pin "9") (pinfunction "EP_9") (pintype "power_in"))
    )
    (net (code "14") (name "GPIO8") (class "Default")
      (node (ref "R1") (pin "2") (pinfunction "2_2") (pintype "passive"))
      (node (ref "U2") (pin "10") (pinfunction "IO8_10") (pintype "bidirectional"))
    )
    (net (code "15") (name "I2C_PW") (class "Default")
      (node (ref "C1") (pin "1") (pinfunction "1_1") (pintype "passive"))
      (node (ref "C2") (pin "1") (pinfunction "1_1") (pintype "passive"))
      (node (ref "R1_PINH") (pin "2") (pinfunction "2_2") (pintype "passive"))
      (node (ref "R2-PINH") (pin "2") (pinfunction "2_2") (pintype "passive"))
      (node (ref "SENSOR2") (pin "2") (pinfunction "CSB_2") (pintype "input"))
      (node (ref "SENSOR2") (pin "6") (pinfunction "VDDIO_6") (pintype "power_in"))
      (node (ref "SENSOR2") (pin "8") (pinfunction "VDD_8") (pintype "power_in"))
      (node (ref "U2") (pin "17") (pinfunction "IO19_17") (pintype "bidirectional"))
    )
    (net (code "16") (name "INT_RTC") (class "Default")
      (node (ref "R1_PINH1") (pin "1") (pinfunction "1_1") (pintype "passive"))
      (node (ref "TP15") (pin "TP") (pinfunction "TP_TP") (pintype "input"))
      (node (ref "U2") (pin "8") (pinfunction "IO0_8") (pintype "bidirectional"))
      (node (ref "U3") (pin "3") (pinfunction "SQW/~{INT}_3") (pintype "output"))
    )
    (net (code "17") (name "IO{slash}BOOT") (class "Default")
      (node (ref "BOOT_BUTTON") (pin "3") (pinfunction "3_3") (pintype "passive"))
      (node (ref "BOOT_BUTTON") (pin "4") (pinfunction "4_4") (pintype "passive"))
      (node (ref "C6") (pin "1") (pinfunction "1_1") (pintype "passive"))
      (node (ref "R_BOOT") (pin "2") (pinfunction "2_2") (pintype "passive"))
      (node (ref "U2") (pin "15") (pinfunction "IO9_15") (pintype "bidirectional"))
    )
    (net (code "18") (name "IO{slash}CHANGE") (class "Default")
      (node (ref "C10") (pin "1") (pinfunction "1_1") (pintype "passive"))
      (node (ref "CHANGE_BUTTON") (pin "3") (pinfunction "3_3") (pintype "passive"))
      (node (ref "CHANGE_BUTTON") (pin "4") (pinfunction "4_4") (pintype "passive"))
      (node (ref "R_CHANGE") (pin "2") (pinfunction "2_2") (pintype "passive"))
      (node (ref "U2") (pin "23") (pinfunction "IO15_23") (pintype "bidirectional"))
    )
    (net (code "19") (name "MISO") (class "Default")
      (node (ref "D12") (pin "1") (pinfunction "1_1") (pintype "passive"))
      (node (ref "J4") (pin "P7") (pinfunction "DAT0_P7") (pintype "bidirectional"))
      (node (ref "R8") (pin "1") (pinfunction "1_1") (pintype "passive"))
      (node (ref "TP6") (pin "TP") (pinfunction "TP_TP") (pintype "input"))
      (node (ref "U1") (pin "2") (pinfunction "DO(IO1)_2") (pintype "bidirectional"))
      (node (ref "U2") (pin "27") (pinfunction "IO2_27") (pintype "bidirectional"))
    )
    (net (code "20") (name "MOSI") (class "Default")
      (node (ref "D11") (pin "1") (pinfunction "1_1") (pintype "passive"))
      (node (ref "J1") (pin "14") (pinfunction "14_14") (pintype "bidirectional"))
      (node (ref "J4") (pin "P3") (pinfunction "CMD_P3") (pintype "bidirectional"))
      (node (ref "R7") (pin "1") (pinfunction "1_1") (pintype "passive"))
      (node (ref "TP7") (pin "TP") (pinfunction "TP_TP") (pintype "input"))
      (node (ref "U1") (pin "5") (pinfunction "DI(IO0)_5") (pintype "bidirectional"))
      (node (ref "U2") (pin "7") (pinfunction "IO7_7") (pintype "bidirectional"))
    )
    (net (code "21") (name "Net-(CHG_LED-PadC)") (class "Default")
      (node (ref "CHG_LED") (pin "C") (pinfunction "C_C") (pintype "passive"))
      (node (ref "R1_BAT") (pin "2") (pinfunction "2_2") (pintype "passive"))
    )
    (net (code "22") (name "Net-(D2-CATHODE)") (class "Default")
      (node (ref "C1_BAT1") (pin "1") (pinfunction "1_1") (pintype "passive"))
      (node (ref "D2") (pin "1") (pinfunction "CATHODE_1") (pintype "bidirectional"))
      (node (ref "IC4") (pin "1") (pinfunction "VIN_1") (pintype "bidirectional"))
      (node (ref "IC4") (pin "3") (pinfunction "CE_3") (pintype "bidirectional"))
      (node (ref "Q1") (pin "2") (pinfunction "S_2") (pintype "bidirectional"))
    )
    (net (code "23") (name "Net-(D3-A)") (class "Default")
      (node (ref "C4") (pin "1") (pinfunction "1_1") (pintype "passive"))
      (node (ref "D3") (pin "2") (pinfunction "A_2") (pintype "bidirectional"))
      (node (ref "D4") (pin "1") (pinfunction "K_1") (pintype "bidirectional"))
    )
    (net (code "24") (name "Net-(D7-CATHODE)") (class "Default")
      (node (ref "D7") (pin "1") (pinfunction "CATHODE_1") (pintype "bidirectional"))
      (node (ref "R_CAPACITOR") (pin "2") (pinfunction "2_2") (pintype "passive"))
    )
    (net (code "25") (name "Net-(EPD_C1-Pad1)") (class "Default")
      (node (ref "EPD_C1") (pin "1") (pinfunction "1_1") (pintype "passive"))
      (node (ref "J1") (pin "4") (pinfunction "4_4") (pintype "bidirectional"))
    )
    (net (code "26") (name "Net-(EPD_C2-Pad1)") (class "Default")
      (node (ref "EPD_C2") (pin "1") (pinfunction "1_1") (pintype "passive"))
      (node (ref "J1") (pin "5") (pinfunction "5_5") (pintype "bidirectional"))
    )
    (net (code "27") (name "Net-(EPD_C6-Pad1)") (class "Default")
      (node (ref "EPD_C6") (pin "1") (pinfunction "1_1") (pintype "passive"))
      (node (ref "J1") (pin "18") (pinfunction "18_18") (pintype "bidirectional"))
    )
    (net (code "28") (name "Net-(EPD_C7-Pad1)") (class "Default")
      (node (ref "EPD_C7") (pin "1") (pinfunction "1_1") (pintype "passive"))
      (node (ref "J1") (pin "19") (pinfunction "19_19") (pintype "bidirectional"))
    )
    (net (code "29") (name "Net-(EPD_C8-Pad1)") (class "Default")
      (node (ref "EPD_C8") (pin "1") (pinfunction "1_1") (pintype "passive"))
      (node (ref "J1") (pin "20") (pinfunction "20_20") (pintype "bidirectional"))
    )
    (net (code "30") (name "Net-(EPD_C10-Pad1)") (class "Default")
      (node (ref "EPD_C10") (pin "1") (pinfunction "1_1") (pintype "passive"))
      (node (ref "J1") (pin "22") (pinfunction "22_22") (pintype "bidirectional"))
    )
    (net (code "31") (name "Net-(EPD_C12-Pad1)") (class "Default")
      (node (ref "EPD_C12") (pin "1") (pinfunction "1_1") (pintype "passive"))
      (node (ref "J1") (pin "24") (pinfunction "24_24") (pintype "bidirectional"))
    )
    (net (code "32") (name "Net-(IC1-CT)") (class "Default")
      (node (ref "C_DELAY") (pin "1") (pinfunction "1_1") (pintype "passive"))
      (node (ref "IC1") (pin "5") (pinfunction "CT_5") (pintype "bidirectional"))
    )
    (net (code "33") (name "Net-(J2-PadA5)") (class "Default")
      (node (ref "J2") (pin "A5") (pinfunction "A5_A5") (pintype "bidirectional"))
      (node (ref "R2-USB1") (pin "2") (pinfunction "2_2") (pintype "passive"))
    )
    (net (code "34") (name "Net-(J2-PadB5)") (class "Default")
      (node (ref "J2") (pin "B5") (pinfunction "B5_B5") (pintype "bidirectional"))
      (node (ref "R2-USB") (pin "1") (pinfunction "1_1") (pintype "passive"))
    )
    (net (code "35") (name "Net-(MCP73831-PROG)") (class "Default")
      (node (ref "MCP73831") (pin "5") (pinfunction "PROG_5") (pintype "input"))
      (node (ref "R2_BAT") (pin "2") (pinfunction "2_2") (pintype "passive"))
    )
    (net (code "36") (name "Net-(MCP73831-STAT)") (class "Default")
      (node (ref "MCP73831") (pin "1") (pinfunction "STAT_1") (pintype "output"))
      (node (ref "R1_BAT") (pin "1") (pinfunction "1_1") (pintype "passive"))
    )
    (net (code "37") (name "PREVGH") (class "Default")
      (node (ref "D5") (pin "1") (pinfunction "K_1") (pintype "bidirectional"))
      (node (ref "EPD_C9") (pin "1") (pinfunction "1_1") (pintype "passive"))
      (node (ref "J1") (pin "21") (pinfunction "21_21") (pintype "bidirectional"))
    )
    (net (code "38") (name "PREVGL") (class "Default")
      (node (ref "D4") (pin "2") (pinfunction "A_2") (pintype "bidirectional"))
      (node (ref "EPD_C11") (pin "1") (pinfunction "1_1") (pintype "passive"))
      (node (ref "J1") (pin "23") (pinfunction "23_23") (pintype "bidirectional"))
    )
    (net (code "39") (name "RESE") (class "Default")
      (node (ref "J1") (pin "3") (pinfunction "3_3") (pintype "bidirectional"))
      (node (ref "Q3") (pin "2") (pinfunction "S_2") (pintype "bidirectional"))
      (node (ref "R3") (pin "1") (pinfunction "1_1") (pintype "passive"))
    )
    (net (code "40") (name "RESE'") (class "Default")
      (node (ref "R2") (pin "2") (pinfunction "2_2") (pintype "passive"))
      (node (ref "R3") (pin "2") (pinfunction "2_2") (pintype "passive"))
      (node (ref "SJ1") (pin "2") (pinfunction "2_2") (pintype "passive"))
    )
    (net (code "41") (name "RESET") (class "Default")
      (node (ref "C5") (pin "1") (pinfunction "1_1") (pintype "passive"))
      (node (ref "IC1") (pin "1") (pinfunction "VOUT_1") (pintype "bidirectional"))
      (node (ref "RESET_BUTTON") (pin "3") (pinfunction "3_3") (pintype "passive"))
      (node (ref "RESET_BUTTON") (pin "4") (pinfunction "4_4") (pintype "passive"))
      (node (ref "R_RESET") (pin "2") (pinfunction "2_2") (pintype "passive"))
      (node (ref "U2") (pin "3") (pinfunction "EN_3") (pintype "input"))
    )
    (net (code "42") (name "RTC_RST") (class "Default")
      (node (ref "U2") (pin "16") (pinfunction "IO18_16") (pintype "bidirectional"))
      (node (ref "U3") (pin "4") (pinfunction "~{RST}_4") (pintype "input"))
    )
    (net (code "43") (name "RX") (class "Default")
      (node (ref "TP2") (pin "TP") (pinfunction "TP_TP") (pintype "input"))
      (node (ref "U2") (pin "24") (pinfunction "RXD0/GPIO17_24") (pintype "bidirectional"))
    )
    (net (code "44") (name "SCK") (class "Default")
      (node (ref "D10") (pin "1") (pinfunction "1_1") (pintype "passive"))
      (node (ref "J1") (pin "13") (pinfunction "13_13") (pintype "bidirectional"))
      (node (ref "J4") (pin "P5") (pinfunction "CLK_P5") (pintype "bidirectional"))
      (node (ref "R6") (pin "1") (pinfunction "1_1") (pintype "passive"))
      (node (ref "TP8") (pin "TP") (pinfunction "TP_TP") (pintype "input"))
      (node (ref "U1") (pin "6") (pinfunction "CLK_6") (pintype "input"))
      (node (ref "U2") (pin "6") (pinfunction "IO6_6") (pintype "bidirectional"))
    )
    (net (code "45") (name "SCL") (class "Default")
      (node (ref "J3") (pin "4") (pinfunction "4_4") (pintype "passive"))
      (node (ref "R2-PINH") (pin "1") (pinfunction "1_1") (pintype "passive"))
      (node (ref "SENSOR2") (pin "4") (pinfunction "SCK_4") (pintype "input"))
      (node (ref "U2") (pin "20") (pinfunction "IO22_20") (pintype "bidirectional"))
      (node (ref "U3") (pin "16") (pinfunction "SCL_16") (pintype "input"))
      (node (ref "U4") (pin "7") (pinfunction "SCL_7") (pintype "input"))
    )
    (net (code "46") (name "SDA") (class "Default")
      (node (ref "J3") (pin "3") (pinfunction "3_3") (pintype "passive"))
      (node (ref "R1_PINH") (pin "1") (pinfunction "1_1") (pintype "passive"))
      (node (ref "SENSOR2") (pin "3") (pinfunction "SDI_3") (pintype "bidirectional"))
      (node (ref "U2") (pin "19") (pinfunction "IO21_19") (pintype "bidirectional"))
      (node (ref "U3") (pin "15") (pinfunction "SDA_15") (pintype "bidirectional"))
      (node (ref "U4") (pin "8") (pinfunction "SDA_8") (pintype "bidirectional"))
    )
    (net (code "47") (name "SRC") (class "Default")
      (node (ref "C4") (pin "2") (pinfunction "2_2") (pintype "passive"))
      (node (ref "D5") (pin "2") (pinfunction "A_2") (pintype "bidirectional"))
      (node (ref "L1") (pin "1") (pinfunction "1_1") (pintype "passive"))
      (node (ref "Q3") (pin "3") (pinfunction "D_3") (pintype "bidirectional"))
    )
    (net (code "48") (name "SS_SD") (class "Default")
      (node (ref "D8") (pin "1") (pinfunction "1_1") (pintype "passive"))
      (node (ref "J4") (pin "P2") (pinfunction "CD/DAT3_P2") (pintype "bidirectional"))
      (node (ref "R10") (pin "1") (pinfunction "1_1") (pintype "passive"))
      (node (ref "U2") (pin "4") (pinfunction "IO4_4") (pintype "bidirectional"))
    )
    (net (code "49") (name "TX") (class "Default")
      (node (ref "TP1") (pin "TP") (pinfunction "TP_TP") (pintype "input"))
      (node (ref "U2") (pin "25") (pinfunction "TXD0/GPIO16_25") (pintype "bidirectional"))
    )
    (net (code "50") (name "USB_D+") (class "Default")
      (node (ref "D1") (pin "1") (pinfunction "I/O1_1_1") (pintype "bidirectional"))
      (node (ref "U2") (pin "14") (pinfunction "IO13_14") (pintype "bidirectional"))
    )
    (net (code "51") (name "USB_D-") (class "Default")
      (node (ref "D1") (pin "3") (pinfunction "I/O2_1_3") (pintype "bidirectional"))
      (node (ref "U2") (pin "13") (pinfunction "IO12_13") (pintype "bidirectional"))
    )
    (net (code "52") (name "VBAT") (class "Default")
      (node (ref "C2_BAT") (pin "1") (pinfunction "1_1") (pintype "passive"))
      (node (ref "MCP73831") (pin "3") (pinfunction "VBAT_3") (pintype "power_in"))
      (node (ref "Q1") (pin "3") (pinfunction "D_3") (pintype "bidirectional"))
      (node (ref "TP3") (pin "TP") (pinfunction "TP_TP") (pintype "input"))
      (node (ref "U4") (pin "2") (pinfunction "CELL_2") (pintype "power_in"))
      (node (ref "U4") (pin "3") (pinfunction "VDD_3") (pintype "power_in"))
    )
    (net (code "53") (name "VBUS") (class "Default")
      (node (ref "C1_BAT") (pin "1") (pinfunction "1_1") (pintype "passive"))
      (node (ref "C4_USB") (pin "1") (pinfunction "1_1") (pintype "passive"))
      (node (ref "C5_USB") (pin "1") (pinfunction "1_1") (pintype "passive"))
      (node (ref "CHG_LED") (pin "A") (pinfunction "A_A") (pintype "passive"))
      (node (ref "D1") (pin "5") (pinfunction "VBUS_5") (pintype "bidirectional"))
      (node (ref "D2") (pin "2") (pinfunction "ANODE_2") (pintype "bidirectional"))
      (node (ref "MCP73831") (pin "4") (pinfunction "VIN_4") (pintype "power_in"))
      (node (ref "PFMF.050.1") (pin "2") (pinfunction "2_2") (pintype "passive"))
      (node (ref "Q1") (pin "1") (pinfunction "G_1") (pintype "bidirectional"))
      (node (ref "R1_PWRUSB") (pin "2") (pinfunction "2_2") (pintype "passive"))
      (node (ref "TP14") (pin "TP") (pinfunction "TP_TP") (pintype "input"))
    )
    (net (code "54") (name "VRTC") (class "Default")
      (node (ref "C10_SUPERCAP") (pin "2") (pinfunction "2_2") (pintype "passive"))
      (node (ref "C8") (pin "1") (pinfunction "1_1") (pintype "passive"))
      (node (ref "R_CAPACITOR") (pin "1") (pinfunction "1_1") (pintype "passive"))
      (node (ref "U3") (pin "14") (pinfunction "VBAT_14") (pintype "power_in"))
    )
    (net (code "55") (name "VUSB") (class "Default")
      (node (ref "J2") (pin "A4") (pinfunction "A4_A4") (pintype "bidirectional"))
      (node (ref "J2") (pin "A9") (pinfunction "A9_A9") (pintype "bidirectional"))
      (node (ref "J2") (pin "B4") (pinfunction "B4_B4") (pintype "bidirectional"))
      (node (ref "J2") (pin "B9") (pinfunction "B9_B9") (pintype "bidirectional"))
      (node (ref "PFMF.050.1") (pin "1") (pinfunction "1_1") (pintype "passive"))
    )
    (net (code "56") (name "unconnected-(IC1-NC-Pad4)") (class "Default")
      (node (ref "IC1") (pin "4") (pinfunction "NC_4") (pintype "no_connect"))
    )
    (net (code "57") (name "unconnected-(IC4-NC-Pad4)") (class "Default")
      (node (ref "IC4") (pin "4") (pinfunction "NC_4") (pintype "no_connect"))
    )
    (net (code "58") (name "unconnected-(J1-Pad1)") (class "Default")
      (node (ref "J1") (pin "1") (pinfunction "1_1") (pintype "bidirectional"))
    )
    (net (code "59") (name "unconnected-(J1-Pad6)") (class "Default")
      (node (ref "J1") (pin "6") (pinfunction "6_6") (pintype "bidirectional"))
    )
    (net (code "60") (name "unconnected-(J1-Pad7)") (class "Default")
      (node (ref "J1") (pin "7") (pinfunction "7_7") (pintype "bidirectional"))
    )
    (net (code "61") (name "unconnected-(J2-PadA8)") (class "Default")
      (node (ref "J2") (pin "A8") (pinfunction "A8_A8") (pintype "bidirectional"))
    )
    (net (code "62") (name "unconnected-(J2-PadB8)") (class "Default")
      (node (ref "J2") (pin "B8") (pinfunction "B8_B8") (pintype "bidirectional"))
    )
    (net (code "63") (name "unconnected-(J4-DAT1-PadP8)") (class "Default")
      (node (ref "J4") (pin "P8") (pinfunction "DAT1_P8") (pintype "bidirectional"))
    )
    (net (code "64") (name "unconnected-(J4-DAT2-PadP1)") (class "Default")
      (node (ref "J4") (pin "P1") (pinfunction "DAT2_P1") (pintype "bidirectional"))
    )
    (net (code "65") (name "unconnected-(J4-DETECTION_1-PadS1)") (class "Default")
      (node (ref "J4") (pin "S1") (pinfunction "DETECTION_1_S1") (pintype "bidirectional"))
    )
    (net (code "66") (name "unconnected-(J4-DETECTION_2-PadS2)") (class "Default")
      (node (ref "J4") (pin "S2") (pinfunction "DETECTION_2_S2") (pintype "bidirectional"))
    )
    (net (code "67") (name "unconnected-(U2-NC-Pad22)") (class "Default")
      (node (ref "U2") (pin "22") (pinfunction "NC_22") (pintype "no_connect"))
    )
    (net (code "68") (name "unconnected-(U4-~{ALERT}-Pad5)") (class "Default")
      (node (ref "U4") (pin "5") (pinfunction "~{ALERT}_5") (pintype "output"))
    )
  )
)
